# FeetHEizer_-_Copy.net
KiCad netlist of a schematic drawn in EAGLE
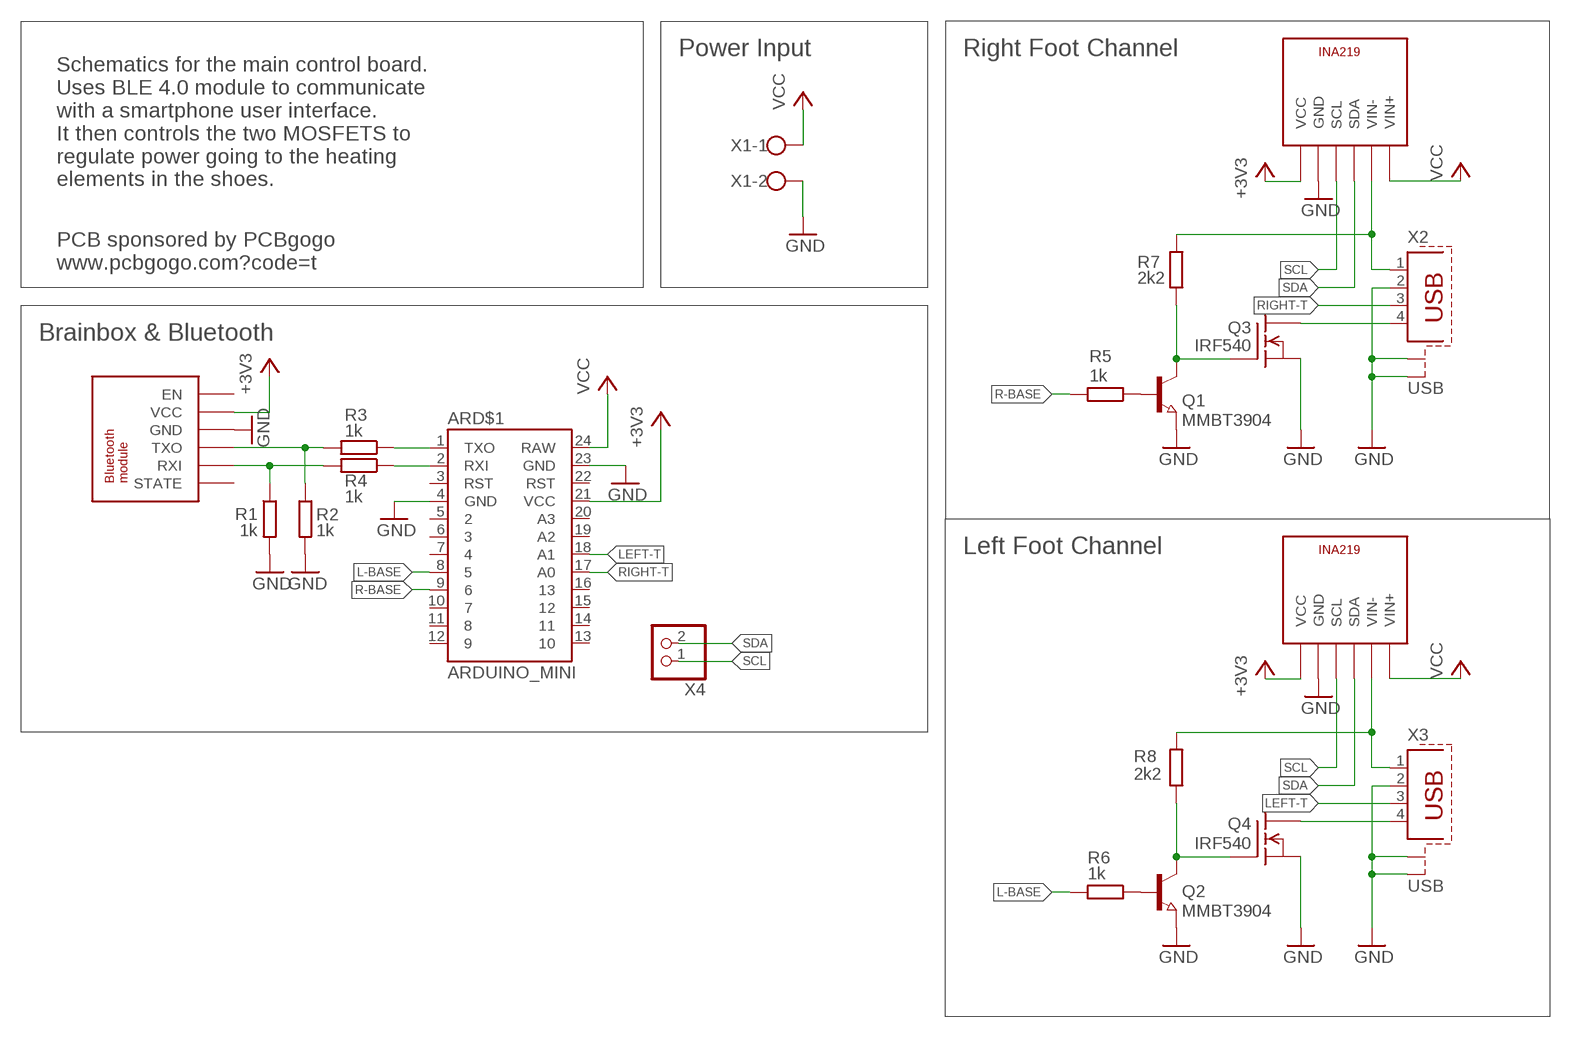
[diagram p0: schematic, sheet 1]

(export (version "E")
  (design (tool "Eeschema 10.0.6"))
  (components
    (comp (ref "ARD$1")
      (value "ARDUINO_MINI")
      (footprint "eagle-import:ARDUINO_MINI")
      (libsource (lib "eagle-import") (part "ARDUINO_MINI"))
    )
    (comp (ref "MODULE1")
      (value "BT")
      (footprint "eagle-import:HC10")
      (libsource (lib "eagle-import") (part "BT"))
    )
    (comp (ref "MODULE2")
      (value "INA")
      (footprint "eagle-import:INA")
      (libsource (lib "eagle-import") (part "INA"))
    )
    (comp (ref "MODULE3")
      (value "INA")
      (footprint "eagle-import:INA")
      (libsource (lib "eagle-import") (part "INA"))
    )
    (comp (ref "Q1")
      (value "MMBT3904")
      (footprint "eagle-import:SOT23")
      (libsource (lib "eagle-import") (part "NPN-TRANSISTOR_SOT23"))
    )
    (comp (ref "Q2")
      (value "MMBT3904")
      (footprint "eagle-import:SOT23")
      (libsource (lib "eagle-import") (part "NPN-TRANSISTOR_SOT23"))
    )
    (comp (ref "Q3")
      (value "IRF540")
      (footprint "eagle-import:TO220")
      (libsource (lib "eagle-import") (part "IRF540"))
    )
    (comp (ref "Q4")
      (value "IRF540")
      (footprint "eagle-import:TO220")
      (libsource (lib "eagle-import") (part "IRF540"))
    )
    (comp (ref "R1")
      (value "1k")
      (footprint "eagle-import:R0805")
      (libsource (lib "eagle-import") (part "R-EU_R0805"))
    )
    (comp (ref "R2")
      (value "1k")
      (footprint "eagle-import:R0805")
      (libsource (lib "eagle-import") (part "R-EU_R0805"))
    )
    (comp (ref "R3")
      (value "1k")
      (footprint "eagle-import:R0805")
      (libsource (lib "eagle-import") (part "R-EU_R0805"))
    )
    (comp (ref "R4")
      (value "1k")
      (footprint "eagle-import:R0805")
      (libsource (lib "eagle-import") (part "R-EU_R0805"))
    )
    (comp (ref "R5")
      (value "1k")
      (footprint "eagle-import:R0805")
      (libsource (lib "eagle-import") (part "R-EU_R0805"))
    )
    (comp (ref "R6")
      (value "1k")
      (footprint "eagle-import:R0805")
      (libsource (lib "eagle-import") (part "R-EU_R0805"))
    )
    (comp (ref "R7")
      (value "2k2")
      (footprint "eagle-import:R0805")
      (libsource (lib "eagle-import") (part "R-EU_R0805"))
    )
    (comp (ref "R8")
      (value "2k2")
      (footprint "eagle-import:R0805")
      (libsource (lib "eagle-import") (part "R-EU_R0805"))
    )
    (comp (ref "X1")
      (value "W237-102")
      (footprint "eagle-import:W237-102")
      (fields (field (name "MPN") "237-102"))
      (libsource (lib "eagle-import") (part "W237-102"))
    )
    (comp (ref "X2")
      (value "USB")
      (footprint "eagle-import:PN87520-S")
      (libsource (lib "eagle-import") (part "USB"))
    )
    (comp (ref "X3")
      (value "USB")
      (footprint "eagle-import:PN87520-S")
      (libsource (lib "eagle-import") (part "USB"))
    )
    (comp (ref "X4")
      (value "PINHD-1X2_2.54")
      (footprint "eagle-import:1X02")
      (libsource (lib "eagle-import") (part "PINHD-1X2_2.54"))
    )
  )
  (nets
    (net (code "1") (name "+3V3") (class "Default")
      (node (ref "ARD$1") (pin "21") (pinfunction "VCC_21") (pintype "bidirectional"))
      (node (ref "MODULE1") (pin "VCC") (pinfunction "VCC_VCC") (pintype "power_in"))
      (node (ref "MODULE2") (pin "VCC") (pinfunction "VCC_VCC") (pintype "power_in"))
      (node (ref "MODULE3") (pin "VCC") (pinfunction "VCC_VCC") (pintype "power_in"))
    )
    (net (code "2") (name "GND") (class "Default")
      (node (ref "ARD$1") (pin "23") (pinfunction "GND_23") (pintype "bidirectional"))
      (node (ref "ARD$1") (pin "4") (pinfunction "GND_4") (pintype "bidirectional"))
      (node (ref "MODULE1") (pin "GND") (pinfunction "GND_GND") (pintype "power_in"))
      (node (ref "MODULE2") (pin "GND") (pinfunction "GND_GND") (pintype "power_in"))
      (node (ref "MODULE3") (pin "GND") (pinfunction "GND_GND") (pintype "power_in"))
      (node (ref "Q1") (pin "2") (pinfunction "E_2") (pintype "passive"))
      (node (ref "Q2") (pin "2") (pinfunction "E_2") (pintype "passive"))
      (node (ref "Q3") (pin "3") (pinfunction "S_3") (pintype "passive"))
      (node (ref "Q4") (pin "3") (pinfunction "S_3") (pintype "passive"))
      (node (ref "R1") (pin "2") (pinfunction "2_2") (pintype "passive"))
      (node (ref "R2") (pin "2") (pinfunction "2_2") (pintype "passive"))
      (node (ref "X1") (pin "2") (pinfunction "KL_2") (pintype "passive"))
      (node (ref "X2") (pin "2") (pinfunction "2_2") (pintype "passive"))
      (node (ref "X2") (pin "S1") (pinfunction "S1_S1") (pintype "passive"))
      (node (ref "X2") (pin "S2") (pinfunction "S2_S2") (pintype "passive"))
      (node (ref "X3") (pin "2") (pinfunction "2_2") (pintype "passive"))
      (node (ref "X3") (pin "S1") (pinfunction "S1_S1") (pintype "passive"))
      (node (ref "X3") (pin "S2") (pinfunction "S2_S2") (pintype "passive"))
    )
    (net (code "3") (name "L-BASE") (class "Default")
      (node (ref "ARD$1") (pin "8") (pinfunction "5_8") (pintype "bidirectional"))
      (node (ref "R6") (pin "2") (pinfunction "2_2") (pintype "passive"))
    )
    (net (code "4") (name "LEFT-T") (class "Default")
      (node (ref "ARD$1") (pin "18") (pinfunction "A1_18") (pintype "bidirectional"))
      (node (ref "X3") (pin "3") (pinfunction "3_3") (pintype "passive"))
    )
    (net (code "5") (name "Net-(ARD$1-RXI)") (class "Default")
      (node (ref "ARD$1") (pin "2") (pinfunction "RXI_2") (pintype "bidirectional"))
      (node (ref "R4") (pin "1") (pinfunction "1_1") (pintype "passive"))
    )
    (net (code "6") (name "Net-(ARD$1-TXO)") (class "Default")
      (node (ref "ARD$1") (pin "1") (pinfunction "TXO_1") (pintype "bidirectional"))
      (node (ref "R3") (pin "1") (pinfunction "1_1") (pintype "passive"))
    )
    (net (code "7") (name "Net-(MODULE1-RXI)") (class "Default")
      (node (ref "MODULE1") (pin "RXD") (pinfunction "RXI_RXD") (pintype "input"))
      (node (ref "R1") (pin "1") (pinfunction "1_1") (pintype "passive"))
      (node (ref "R4") (pin "2") (pinfunction "2_2") (pintype "passive"))
    )
    (net (code "8") (name "Net-(MODULE1-TXO)") (class "Default")
      (node (ref "MODULE1") (pin "TXD") (pinfunction "TXO_TXD") (pintype "output"))
      (node (ref "R2") (pin "1") (pinfunction "1_1") (pintype "passive"))
      (node (ref "R3") (pin "2") (pinfunction "2_2") (pintype "passive"))
    )
    (net (code "9") (name "Net-(MODULE2-PadVIN-)") (class "Default")
      (node (ref "MODULE2") (pin "VIN-") (pinfunction "VIN-_VIN-") (pintype "bidirectional"))
      (node (ref "R7") (pin "2") (pinfunction "2_2") (pintype "passive"))
      (node (ref "X2") (pin "1") (pinfunction "1_1") (pintype "passive"))
    )
    (net (code "10") (name "Net-(MODULE3-PadVIN-)") (class "Default")
      (node (ref "MODULE3") (pin "VIN-") (pinfunction "VIN-_VIN-") (pintype "bidirectional"))
      (node (ref "R8") (pin "2") (pinfunction "2_2") (pintype "passive"))
      (node (ref "X3") (pin "1") (pinfunction "1_1") (pintype "passive"))
    )
    (net (code "11") (name "Net-(Q1-B)") (class "Default")
      (node (ref "Q1") (pin "1") (pinfunction "B_1") (pintype "passive"))
      (node (ref "R5") (pin "1") (pinfunction "1_1") (pintype "passive"))
    )
    (net (code "12") (name "Net-(Q1-C)") (class "Default")
      (node (ref "Q1") (pin "3") (pinfunction "C_3") (pintype "passive"))
      (node (ref "Q3") (pin "1") (pinfunction "G_1") (pintype "passive"))
      (node (ref "R7") (pin "1") (pinfunction "1_1") (pintype "passive"))
    )
    (net (code "13") (name "Net-(Q2-B)") (class "Default")
      (node (ref "Q2") (pin "1") (pinfunction "B_1") (pintype "passive"))
      (node (ref "R6") (pin "1") (pinfunction "1_1") (pintype "passive"))
    )
    (net (code "14") (name "Net-(Q2-C)") (class "Default")
      (node (ref "Q2") (pin "3") (pinfunction "C_3") (pintype "passive"))
      (node (ref "Q4") (pin "1") (pinfunction "G_1") (pintype "passive"))
      (node (ref "R8") (pin "1") (pinfunction "1_1") (pintype "passive"))
    )
    (net (code "15") (name "Net-(Q3-D)") (class "Default")
      (node (ref "Q3") (pin "2") (pinfunction "D_2") (pintype "passive"))
      (node (ref "X2") (pin "4") (pinfunction "4_4") (pintype "passive"))
    )
    (net (code "16") (name "Net-(Q4-D)") (class "Default")
      (node (ref "Q4") (pin "2") (pinfunction "D_2") (pintype "passive"))
      (node (ref "X3") (pin "4") (pinfunction "4_4") (pintype "passive"))
    )
    (net (code "17") (name "R-BASE") (class "Default")
      (node (ref "ARD$1") (pin "9") (pinfunction "6_9") (pintype "bidirectional"))
      (node (ref "R5") (pin "2") (pinfunction "2_2") (pintype "passive"))
    )
    (net (code "18") (name "RIGHT-T") (class "Default")
      (node (ref "ARD$1") (pin "17") (pinfunction "A0_17") (pintype "bidirectional"))
      (node (ref "X2") (pin "3") (pinfunction "3_3") (pintype "passive"))
    )
    (net (code "19") (name "SCL") (class "Default")
      (node (ref "MODULE2") (pin "SCL") (pinfunction "SCL_SCL") (pintype "bidirectional"))
      (node (ref "MODULE3") (pin "SCL") (pinfunction "SCL_SCL") (pintype "bidirectional"))
      (node (ref "X4") (pin "1") (pinfunction "1_1") (pintype "passive"))
    )
    (net (code "20") (name "SDA") (class "Default")
      (node (ref "MODULE2") (pin "SDA") (pinfunction "SDA_SDA") (pintype "bidirectional"))
      (node (ref "MODULE3") (pin "SDA") (pinfunction "SDA_SDA") (pintype "bidirectional"))
      (node (ref "X4") (pin "2") (pinfunction "2_2") (pintype "passive"))
    )
    (net (code "21") (name "VCC") (class "Default")
      (node (ref "ARD$1") (pin "24") (pinfunction "RAW_24") (pintype "bidirectional"))
      (node (ref "MODULE2") (pin "VIN+") (pinfunction "VIN+_VIN+") (pintype "bidirectional"))
      (node (ref "MODULE3") (pin "VIN+") (pinfunction "VIN+_VIN+") (pintype "bidirectional"))
      (node (ref "X1") (pin "1") (pinfunction "KL_1") (pintype "passive"))
    )
    (net (code "22") (name "unconnected-(ARD$1-2-Pad5)") (class "Default")
      (node (ref "ARD$1") (pin "5") (pinfunction "2_5") (pintype "bidirectional"))
    )
    (net (code "23") (name "unconnected-(ARD$1-3-Pad6)") (class "Default")
      (node (ref "ARD$1") (pin "6") (pinfunction "3_6") (pintype "bidirectional"))
    )
    (net (code "24") (name "unconnected-(ARD$1-4-Pad7)") (class "Default")
      (node (ref "ARD$1") (pin "7") (pinfunction "4_7") (pintype "bidirectional"))
    )
    (net (code "25") (name "unconnected-(ARD$1-7-Pad10)") (class "Default")
      (node (ref "ARD$1") (pin "10") (pinfunction "7_10") (pintype "bidirectional"))
    )
    (net (code "26") (name "unconnected-(ARD$1-8-Pad11)") (class "Default")
      (node (ref "ARD$1") (pin "11") (pinfunction "8_11") (pintype "bidirectional"))
    )
    (net (code "27") (name "unconnected-(ARD$1-9-Pad12)") (class "Default")
      (node (ref "ARD$1") (pin "12") (pinfunction "9_12") (pintype "bidirectional"))
    )
    (net (code "28") (name "unconnected-(ARD$1-10-Pad13)") (class "Default")
      (node (ref "ARD$1") (pin "13") (pinfunction "10_13") (pintype "bidirectional"))
    )
    (net (code "29") (name "unconnected-(ARD$1-11-Pad14)") (class "Default")
      (node (ref "ARD$1") (pin "14") (pinfunction "11_14") (pintype "bidirectional"))
    )
    (net (code "30") (name "unconnected-(ARD$1-12-Pad15)") (class "Default")
      (node (ref "ARD$1") (pin "15") (pinfunction "12_15") (pintype "bidirectional"))
    )
    (net (code "31") (name "unconnected-(ARD$1-13-Pad16)") (class "Default")
      (node (ref "ARD$1") (pin "16") (pinfunction "13_16") (pintype "bidirectional"))
    )
    (net (code "32") (name "unconnected-(ARD$1-A2-Pad19)") (class "Default")
      (node (ref "ARD$1") (pin "19") (pinfunction "A2_19") (pintype "bidirectional"))
    )
    (net (code "33") (name "unconnected-(ARD$1-A3-Pad20)") (class "Default")
      (node (ref "ARD$1") (pin "20") (pinfunction "A3_20") (pintype "bidirectional"))
    )
    (net (code "34") (name "unconnected-(ARD$1-RST-Pad3)") (class "Default")
      (node (ref "ARD$1") (pin "3") (pinfunction "RST_3") (pintype "bidirectional"))
    )
    (net (code "35") (name "unconnected-(ARD$1-RST-Pad22)") (class "Default")
      (node (ref "ARD$1") (pin "22") (pinfunction "RST_22") (pintype "bidirectional"))
    )
    (net (code "36") (name "unconnected-(MODULE1-PadEN)") (class "Default")
      (node (ref "MODULE1") (pin "EN") (pinfunction "EN_EN") (pintype "input"))
    )
    (net (code "37") (name "unconnected-(MODULE1-PadSTATE)") (class "Default")
      (node (ref "MODULE1") (pin "STATE") (pinfunction "STATE_STATE") (pintype "output"))
    )
  )
)
